# Sheet1.net
KiCad netlist of a schematic drawn in Altium Designer
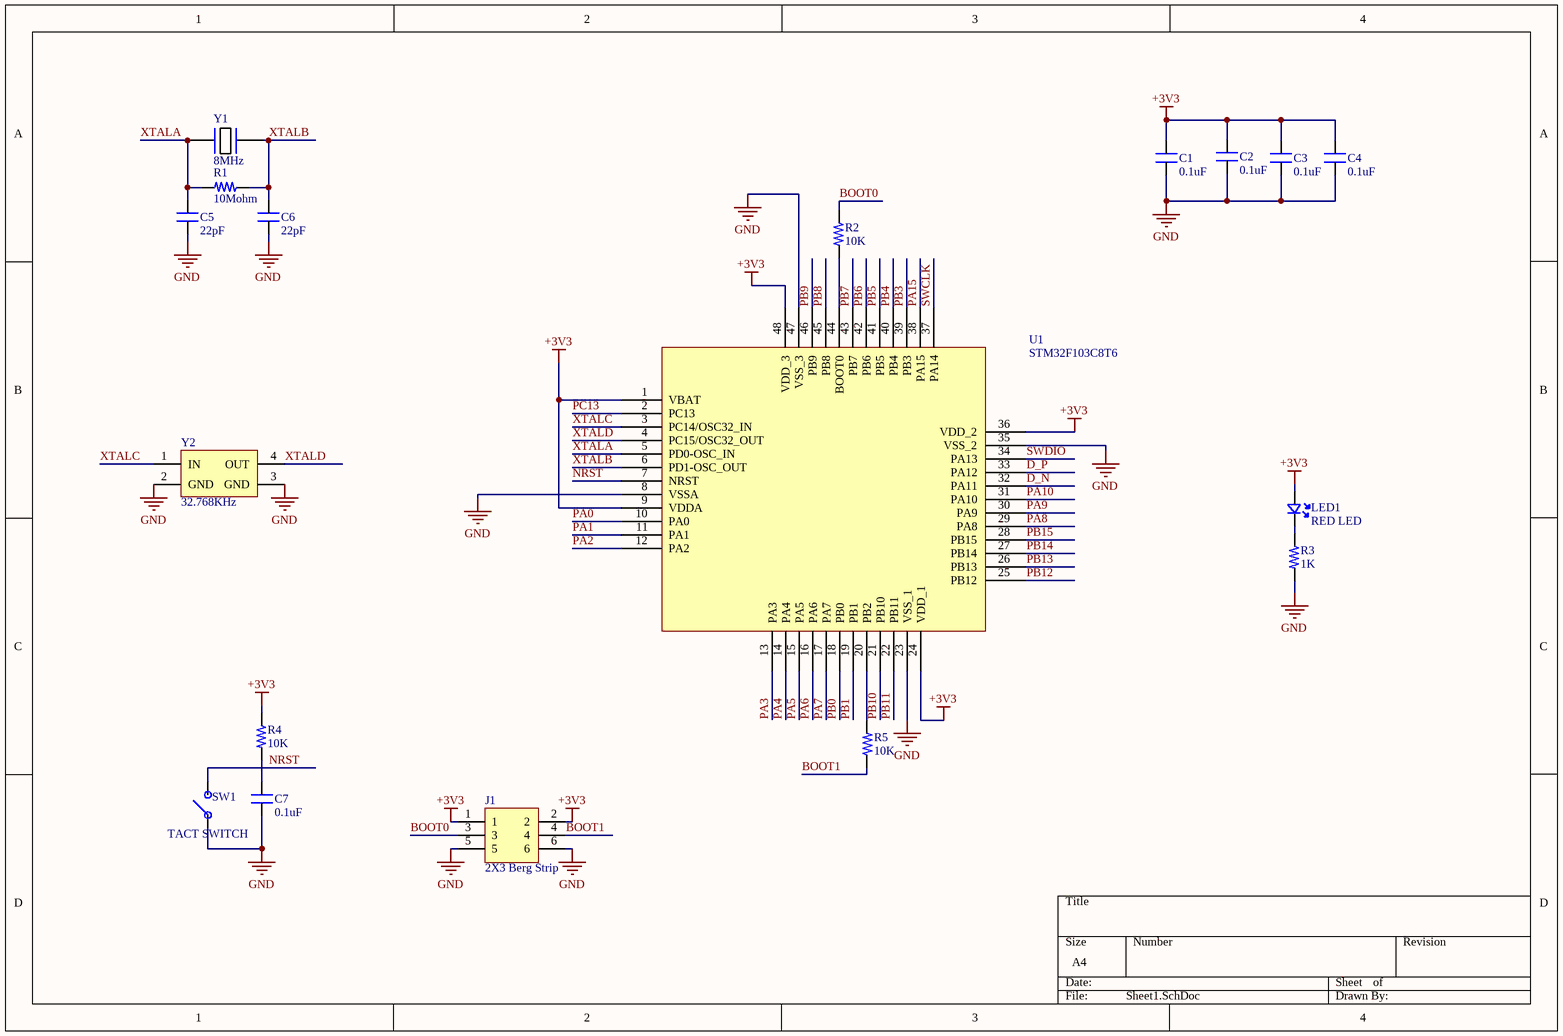
[diagram p0: Sheet1.SchDoc]

(export (version "E")
  (design (tool "Eeschema 10.0.6"))
  (components
    (comp (ref "C1")
      (value "0.1uF")
      (footprint "CAP_0805")
      (description "0.1µF ±5% 50V Ceramic Capacitor X7R 0805 (2012 Metric)")
      (fields
        (field (name "MANUFACTURER") "KEMET")
        (field (name "MANUFACTURING PART NUMBER") "C0805C104J5RACTU")
      )
      (libsource (lib "STM_SCH_LIB") (part "CAP_0.1uF-50V-5%-0805"))
    )
    (comp (ref "C2")
      (value "0.1uF")
      (footprint "CAP_0805")
      (description "0.1µF ±5% 50V Ceramic Capacitor X7R 0805 (2012 Metric)")
      (fields
        (field (name "MANUFACTURER") "KEMET")
        (field (name "MANUFACTURING PART NUMBER") "C0805C104J5RACTU")
      )
      (libsource (lib "STM_SCH_LIB") (part "CAP_0.1uF-50V-5%-0805"))
    )
    (comp (ref "C3")
      (value "0.1uF")
      (footprint "CAP_0805")
      (description "0.1µF ±5% 50V Ceramic Capacitor X7R 0805 (2012 Metric)")
      (fields
        (field (name "MANUFACTURER") "KEMET")
        (field (name "MANUFACTURING PART NUMBER") "C0805C104J5RACTU")
      )
      (libsource (lib "STM_SCH_LIB") (part "CAP_0.1uF-50V-5%-0805"))
    )
    (comp (ref "C4")
      (value "0.1uF")
      (footprint "CAP_0805")
      (description "0.1µF ±5% 50V Ceramic Capacitor X7R 0805 (2012 Metric)")
      (fields
        (field (name "MANUFACTURER") "KEMET")
        (field (name "MANUFACTURING PART NUMBER") "C0805C104J5RACTU")
      )
      (libsource (lib "STM_SCH_LIB") (part "CAP_0.1uF-50V-5%-0805"))
    )
    (comp (ref "C5")
      (value "22pF")
      (footprint "CAP_0805")
      (description "22pF ±5% 50V Ceramic Capacitor C0G, NP0 0805 (2012 Metric)")
      (fields
        (field (name "MANUFACTURER") "KEMET")
        (field (name "MANUFACTURER PART NUMBER") "C0805C220J5GACTU")
      )
      (libsource (lib "STM_SCH_LIB") (part "CAP_22pF-50V-5%-0805"))
    )
    (comp (ref "C6")
      (value "22pF")
      (footprint "CAP_0805")
      (description "22pF ±5% 50V Ceramic Capacitor C0G, NP0 0805 (2012 Metric)")
      (fields
        (field (name "MANUFACTURER") "KEMET")
        (field (name "MANUFACTURER PART NUMBER") "C0805C220J5GACTU")
      )
      (libsource (lib "STM_SCH_LIB") (part "CAP_22pF-50V-5%-0805"))
    )
    (comp (ref "C7")
      (value "0.1uF")
      (footprint "CAP_0805")
      (description "0.1µF ±5% 50V Ceramic Capacitor X7R 0805 (2012 Metric)")
      (fields
        (field (name "MANUFACTURER") "KEMET")
        (field (name "MANUFACTURING PART NUMBER") "C0805C104J5RACTU")
      )
      (libsource (lib "STM_SCH_LIB") (part "CAP_0.1uF-50V-5%-0805"))
    )
    (comp (ref "J1")
      (value "2X3 Berg Strip")
      (footprint "CON6_100_59D78_TH_ST_Duplicate")
      (description "6 pin, 2 row, 2.54mm pitch bergstrip")
      (fields (field (name "MANUFACTURER") "NA"))
      (libsource (lib "STM_SCH_LIB") (part "CON-BS-PLG_2X3-100-TH-ST"))
    )
    (comp (ref "LED1")
      (value "RED LED")
      (footprint "LED_0805")
      (description "Red 621nm LED Indication - Discrete 2V 0805 (2012 Metric)")
      (fields
        (field (name "MANUFACTURER") "Lite-On Inc.")
        (field (name "MANUFACTURER PART NUMBER") "LTST-C170EKT")
      )
      (libsource (lib "STM_SCH_LIB") (part "LED-RED_10mA-0805"))
    )
    (comp (ref "R1")
      (value "10Mohm")
      (footprint "RES_0805")
      (fields
        (field (name "MANUFACTURER") "Rohm Semiconductor")
        (field (name "MANUFACTURING PART NUMBER") "KTR10EZPF1005")
      )
      (libsource (lib "STM_SCH_LIB") (part "RES_10MOHM-0.125W-1%-0805"))
    )
    (comp (ref "R2")
      (value "10K")
      (footprint "RES_0805")
      (description "10 kOhms ±1% 0.125W, 1/8W Chip Resistor 0805 (2012 Metric) Moisture Resistant Thick Film")
      (fields
        (field (name "MANUFACTURER") "Yageo")
        (field (name "MANUFACTURING PART NUMBER") "RC0805FR-0710KL")
      )
      (libsource (lib "STM_SCH_LIB") (part "RES_10K-0.125W-1%-0805"))
    )
    (comp (ref "R3")
      (value "1K")
      (footprint "RES_0805")
      (description "1 kOhms ±1% 0.125W, 1/8W Chip Resistor 0805 (2012 Metric) Moisture Resistant Thick Film")
      (fields (field (name "MANUFACTURER") "垈㎵á") (field (name "MANUFACTURER PART NUMBER") "RC0805FR-071KL"))
      (libsource (lib "STM_SCH_LIB") (part "RES_1K-0.125W-1%-0805"))
    )
    (comp (ref "R4")
      (value "10K")
      (footprint "RES_0805")
      (description "10 kOhms ±1% 0.125W, 1/8W Chip Resistor 0805 (2012 Metric) Moisture Resistant Thick Film")
      (fields
        (field (name "MANUFACTURER") "Yageo")
        (field (name "MANUFACTURING PART NUMBER") "RC0805FR-0710KL")
      )
      (libsource (lib "STM_SCH_LIB") (part "RES_10K-0.125W-1%-0805"))
    )
    (comp (ref "R5")
      (value "10K")
      (footprint "RES_0805")
      (description "10 kOhms ±1% 0.125W, 1/8W Chip Resistor 0805 (2012 Metric) Moisture Resistant Thick Film")
      (fields
        (field (name "MANUFACTURER") "Yageo")
        (field (name "MANUFACTURING PART NUMBER") "RC0805FR-0710KL")
      )
      (libsource (lib "STM_SCH_LIB") (part "RES_10K-0.125W-1%-0805"))
    )
    (comp (ref "SW1")
      (value "TACT SWITCH")
      (footprint "SW_342_SMD")
      (description "Tactile Switch SPST-NO Top Actuated Surface Mount")
      (fields (field (name "MANUFACTURER") "C&K") (field (name "MANUFACTURING PART NUMBER") "KSR223GLFG"))
      (libsource (lib "STM_SCH_LIB") (part "SW_KSR223GLFG-SMD"))
    )
    (comp (ref "U1")
      (value "STM32F103C8T6")
      (footprint "LQFP-48_19.6_393_58X11_SMD")
      (description "ARM® Cortex®-M3 STM32F1 Microcontroller IC 32-Bit 72MHz 64KB (64K x 8) FLASH")
      (fields (field (name "MANUFACTURER") "STMicroelectronics"))
      (libsource (lib "STM_SCH_LIB") (part "IC-STM32F103C8T6 _1"))
    )
    (comp (ref "Y1")
      (value "8MHz")
      (footprint "XTAL_314_240X47_SMD")
      (description "Crystals 8MHz 22pF -20C 70C")
      (fields
        (field (name "MANUFACTURER") "IQD Frequency Products")
        (field (name "MANUFACTURING PART NUMBER") "LFXTAL030234Reel")
      )
      (libsource (lib "STM_SCH_LIB") (part "XTAL_8MHZ-LFXTAL030234"))
    )
    (comp (ref "Y2")
      (value "32.768KHz")
      (footprint "XTAL_MC-405 32.7680K-G3")
      (description "Crystals SMD AT XTL MHZ +/-50PPM 12.5 PF 250 T/R")
      (fields
        (field (name "MANUFACTURER") "Epson")
        (field (name "MANUFACTURING PART NUMBER") "MC-405 32.7680K-G3: ROHS")
      )
      (libsource (lib "STM_SCH_LIB") (part "XTAL_32.768KHz-MC-405 32.7680K-G3"))
    )
  )
  (nets
    (net (code "1") (name "+3V3") (class "Default")
      (node (ref "C1") (pin "2") (pinfunction "2_2") (pintype "passive"))
      (node (ref "C2") (pin "2") (pinfunction "2_2") (pintype "passive"))
      (node (ref "C3") (pin "2") (pinfunction "2_2") (pintype "passive"))
      (node (ref "C4") (pin "2") (pinfunction "2_2") (pintype "passive"))
      (node (ref "J1") (pin "1") (pinfunction "1_1") (pintype "passive"))
      (node (ref "J1") (pin "2") (pinfunction "2_2") (pintype "passive"))
      (node (ref "LED1") (pin "A") (pinfunction "A_A") (pintype "passive"))
      (node (ref "R4") (pin "2") (pinfunction "2_2") (pintype "passive"))
      (node (ref "U1") (pin "1") (pinfunction "VBAT_1") (pintype "passive"))
      (node (ref "U1") (pin "24") (pinfunction "VDD_1_24") (pintype "passive"))
      (node (ref "U1") (pin "36") (pinfunction "VDD_2_36") (pintype "passive"))
      (node (ref "U1") (pin "48") (pinfunction "VDD_3_48") (pintype "passive"))
      (node (ref "U1") (pin "9") (pinfunction "VDDA_9") (pintype "passive"))
    )
    (net (code "2") (name "/BOOT0") (class "Default")
      (node (ref "J1") (pin "3") (pinfunction "3_3") (pintype "passive"))
      (node (ref "R2") (pin "2") (pinfunction "2_2") (pintype "passive"))
    )
    (net (code "3") (name "/BOOT1") (class "Default")
      (node (ref "J1") (pin "4") (pinfunction "4_4") (pintype "passive"))
      (node (ref "R5") (pin "2") (pinfunction "2_2") (pintype "passive"))
    )
    (net (code "4") (name "/D_N") (class "Default")
      (node (ref "U1") (pin "32") (pinfunction "PA11_32") (pintype "passive"))
    )
    (net (code "5") (name "/D_P") (class "Default")
      (node (ref "U1") (pin "33") (pinfunction "PA12_33") (pintype "passive"))
    )
    (net (code "6") (name "/NRST") (class "Default")
      (node (ref "SW1") (pin "2") (pinfunction "2_2") (pintype "passive"))
      (node (ref "U1") (pin "7") (pinfunction "NRST_7") (pintype "passive"))
    )
    (net (code "7") (name "/PA0") (class "Default")
      (node (ref "U1") (pin "10") (pinfunction "PA0_10") (pintype "passive"))
    )
    (net (code "8") (name "/PA1") (class "Default")
      (node (ref "U1") (pin "11") (pinfunction "PA1_11") (pintype "passive"))
    )
    (net (code "9") (name "/PA2") (class "Default")
      (node (ref "U1") (pin "12") (pinfunction "PA2_12") (pintype "passive"))
    )
    (net (code "10") (name "/PA3") (class "Default")
      (node (ref "U1") (pin "13") (pinfunction "PA3_13") (pintype "passive"))
    )
    (net (code "11") (name "/PA4") (class "Default")
      (node (ref "U1") (pin "14") (pinfunction "PA4_14") (pintype "passive"))
    )
    (net (code "12") (name "/PA5") (class "Default")
      (node (ref "U1") (pin "15") (pinfunction "PA5_15") (pintype "passive"))
    )
    (net (code "13") (name "/PA6") (class "Default")
      (node (ref "U1") (pin "16") (pinfunction "PA6_16") (pintype "passive"))
    )
    (net (code "14") (name "/PA7") (class "Default")
      (node (ref "U1") (pin "17") (pinfunction "PA7_17") (pintype "passive"))
    )
    (net (code "15") (name "/PA8") (class "Default")
      (node (ref "U1") (pin "29") (pinfunction "PA8_29") (pintype "passive"))
    )
    (net (code "16") (name "/PA9") (class "Default")
      (node (ref "U1") (pin "30") (pinfunction "PA9_30") (pintype "passive"))
    )
    (net (code "17") (name "/PA10") (class "Default")
      (node (ref "U1") (pin "31") (pinfunction "PA10_31") (pintype "passive"))
    )
    (net (code "18") (name "/PA15") (class "Default")
      (node (ref "U1") (pin "38") (pinfunction "PA15_38") (pintype "passive"))
    )
    (net (code "19") (name "/PB0") (class "Default")
      (node (ref "U1") (pin "18") (pinfunction "PB0_18") (pintype "passive"))
    )
    (net (code "20") (name "/PB1") (class "Default")
      (node (ref "U1") (pin "19") (pinfunction "PB1_19") (pintype "passive"))
    )
    (net (code "21") (name "/PB3") (class "Default")
      (node (ref "U1") (pin "39") (pinfunction "PB3_39") (pintype "passive"))
    )
    (net (code "22") (name "/PB4") (class "Default")
      (node (ref "U1") (pin "40") (pinfunction "PB4_40") (pintype "passive"))
    )
    (net (code "23") (name "/PB5") (class "Default")
      (node (ref "U1") (pin "41") (pinfunction "PB5_41") (pintype "passive"))
    )
    (net (code "24") (name "/PB6") (class "Default")
      (node (ref "U1") (pin "42") (pinfunction "PB6_42") (pintype "passive"))
    )
    (net (code "25") (name "/PB7") (class "Default")
      (node (ref "U1") (pin "43") (pinfunction "PB7_43") (pintype "passive"))
    )
    (net (code "26") (name "/PB8") (class "Default")
      (node (ref "U1") (pin "45") (pinfunction "PB8_45") (pintype "passive"))
    )
    (net (code "27") (name "/PB9") (class "Default")
      (node (ref "U1") (pin "46") (pinfunction "PB9_46") (pintype "passive"))
    )
    (net (code "28") (name "/PB10") (class "Default")
      (node (ref "U1") (pin "21") (pinfunction "PB10_21") (pintype "passive"))
    )
    (net (code "29") (name "/PB11") (class "Default")
      (node (ref "U1") (pin "22") (pinfunction "PB11_22") (pintype "passive"))
    )
    (net (code "30") (name "/PB12") (class "Default")
      (node (ref "U1") (pin "25") (pinfunction "PB12_25") (pintype "passive"))
    )
    (net (code "31") (name "/PB13") (class "Default")
      (node (ref "U1") (pin "26") (pinfunction "PB13_26") (pintype "passive"))
    )
    (net (code "32") (name "/PB14") (class "Default")
      (node (ref "U1") (pin "27") (pinfunction "PB14_27") (pintype "passive"))
    )
    (net (code "33") (name "/PB15") (class "Default")
      (node (ref "U1") (pin "28") (pinfunction "PB15_28") (pintype "passive"))
    )
    (net (code "34") (name "/PC13") (class "Default")
      (node (ref "U1") (pin "2") (pinfunction "PC13_2") (pintype "passive"))
    )
    (net (code "35") (name "/SWCLK") (class "Default")
      (node (ref "U1") (pin "37") (pinfunction "PA14_37") (pintype "passive"))
    )
    (net (code "36") (name "/SWDIO") (class "Default")
      (node (ref "U1") (pin "34") (pinfunction "PA13_34") (pintype "passive"))
    )
    (net (code "37") (name "/XTALA") (class "Default")
      (node (ref "C5") (pin "2") (pinfunction "2_2") (pintype "passive"))
      (node (ref "R1") (pin "1") (pinfunction "1_1") (pintype "passive"))
      (node (ref "U1") (pin "5") (pinfunction "PD0-OSC_IN_5") (pintype "passive"))
      (node (ref "Y1") (pin "1") (pinfunction "1_1") (pintype "passive"))
    )
    (net (code "38") (name "/XTALB") (class "Default")
      (node (ref "C6") (pin "2") (pinfunction "2_2") (pintype "passive"))
      (node (ref "R1") (pin "2") (pinfunction "2_2") (pintype "passive"))
      (node (ref "U1") (pin "6") (pinfunction "PD1-OSC_OUT_6") (pintype "passive"))
      (node (ref "Y1") (pin "2") (pinfunction "2_2") (pintype "passive"))
    )
    (net (code "39") (name "/XTALC") (class "Default")
      (node (ref "U1") (pin "3") (pinfunction "PC14/OSC32_IN_3") (pintype "passive"))
      (node (ref "Y2") (pin "1") (pinfunction "IN_1") (pintype "passive"))
    )
    (net (code "40") (name "/XTALD") (class "Default")
      (node (ref "U1") (pin "4") (pinfunction "PC15/OSC32_OUT_4") (pintype "passive"))
      (node (ref "Y2") (pin "4") (pinfunction "OUT_4") (pintype "passive"))
    )
    (net (code "41") (name "GND") (class "Default")
      (node (ref "C1") (pin "1") (pinfunction "1_1") (pintype "passive"))
      (node (ref "C2") (pin "1") (pinfunction "1_1") (pintype "passive"))
      (node (ref "C3") (pin "1") (pinfunction "1_1") (pintype "passive"))
      (node (ref "C4") (pin "1") (pinfunction "1_1") (pintype "passive"))
      (node (ref "C5") (pin "1") (pinfunction "1_1") (pintype "passive"))
      (node (ref "C6") (pin "1") (pinfunction "1_1") (pintype "passive"))
      (node (ref "C7") (pin "1") (pinfunction "1_1") (pintype "passive"))
      (node (ref "J1") (pin "5") (pinfunction "5_5") (pintype "passive"))
      (node (ref "J1") (pin "6") (pinfunction "6_6") (pintype "passive"))
      (node (ref "R3") (pin "1") (pinfunction "1_1") (pintype "passive"))
      (node (ref "SW1") (pin "1") (pinfunction "1_1") (pintype "passive"))
      (node (ref "U1") (pin "23") (pinfunction "VSS_1_23") (pintype "passive"))
      (node (ref "U1") (pin "35") (pinfunction "VSS_2_35") (pintype "passive"))
      (node (ref "U1") (pin "47") (pinfunction "VSS_3_47") (pintype "passive"))
      (node (ref "U1") (pin "8") (pinfunction "VSSA_8") (pintype "passive"))
      (node (ref "Y2") (pin "2") (pinfunction "GND_2") (pintype "passive"))
      (node (ref "Y2") (pin "3") (pinfunction "GND_3") (pintype "passive"))
    )
    (net (code "42") (name "Net-(C7-Pad2)") (class "Default")
      (node (ref "C7") (pin "2") (pinfunction "2_2") (pintype "passive"))
      (node (ref "R4") (pin "1") (pinfunction "1_1") (pintype "passive"))
    )
    (net (code "43") (name "Net-(LED1-PadK)") (class "Default")
      (node (ref "LED1") (pin "K") (pinfunction "K_K") (pintype "passive"))
      (node (ref "R3") (pin "2") (pinfunction "2_2") (pintype "passive"))
    )
    (net (code "44") (name "Net-(U1-BOOT0)") (class "Default")
      (node (ref "R2") (pin "1") (pinfunction "1_1") (pintype "passive"))
      (node (ref "U1") (pin "44") (pinfunction "BOOT0_44") (pintype "passive"))
    )
    (net (code "45") (name "Net-(U1-PB2)") (class "Default")
      (node (ref "R5") (pin "1") (pinfunction "1_1") (pintype "passive"))
      (node (ref "U1") (pin "20") (pinfunction "PB2_20") (pintype "passive"))
    )
  )
)
